# MPU-9250_Breakout.net
KiCad netlist of a schematic drawn in EAGLE
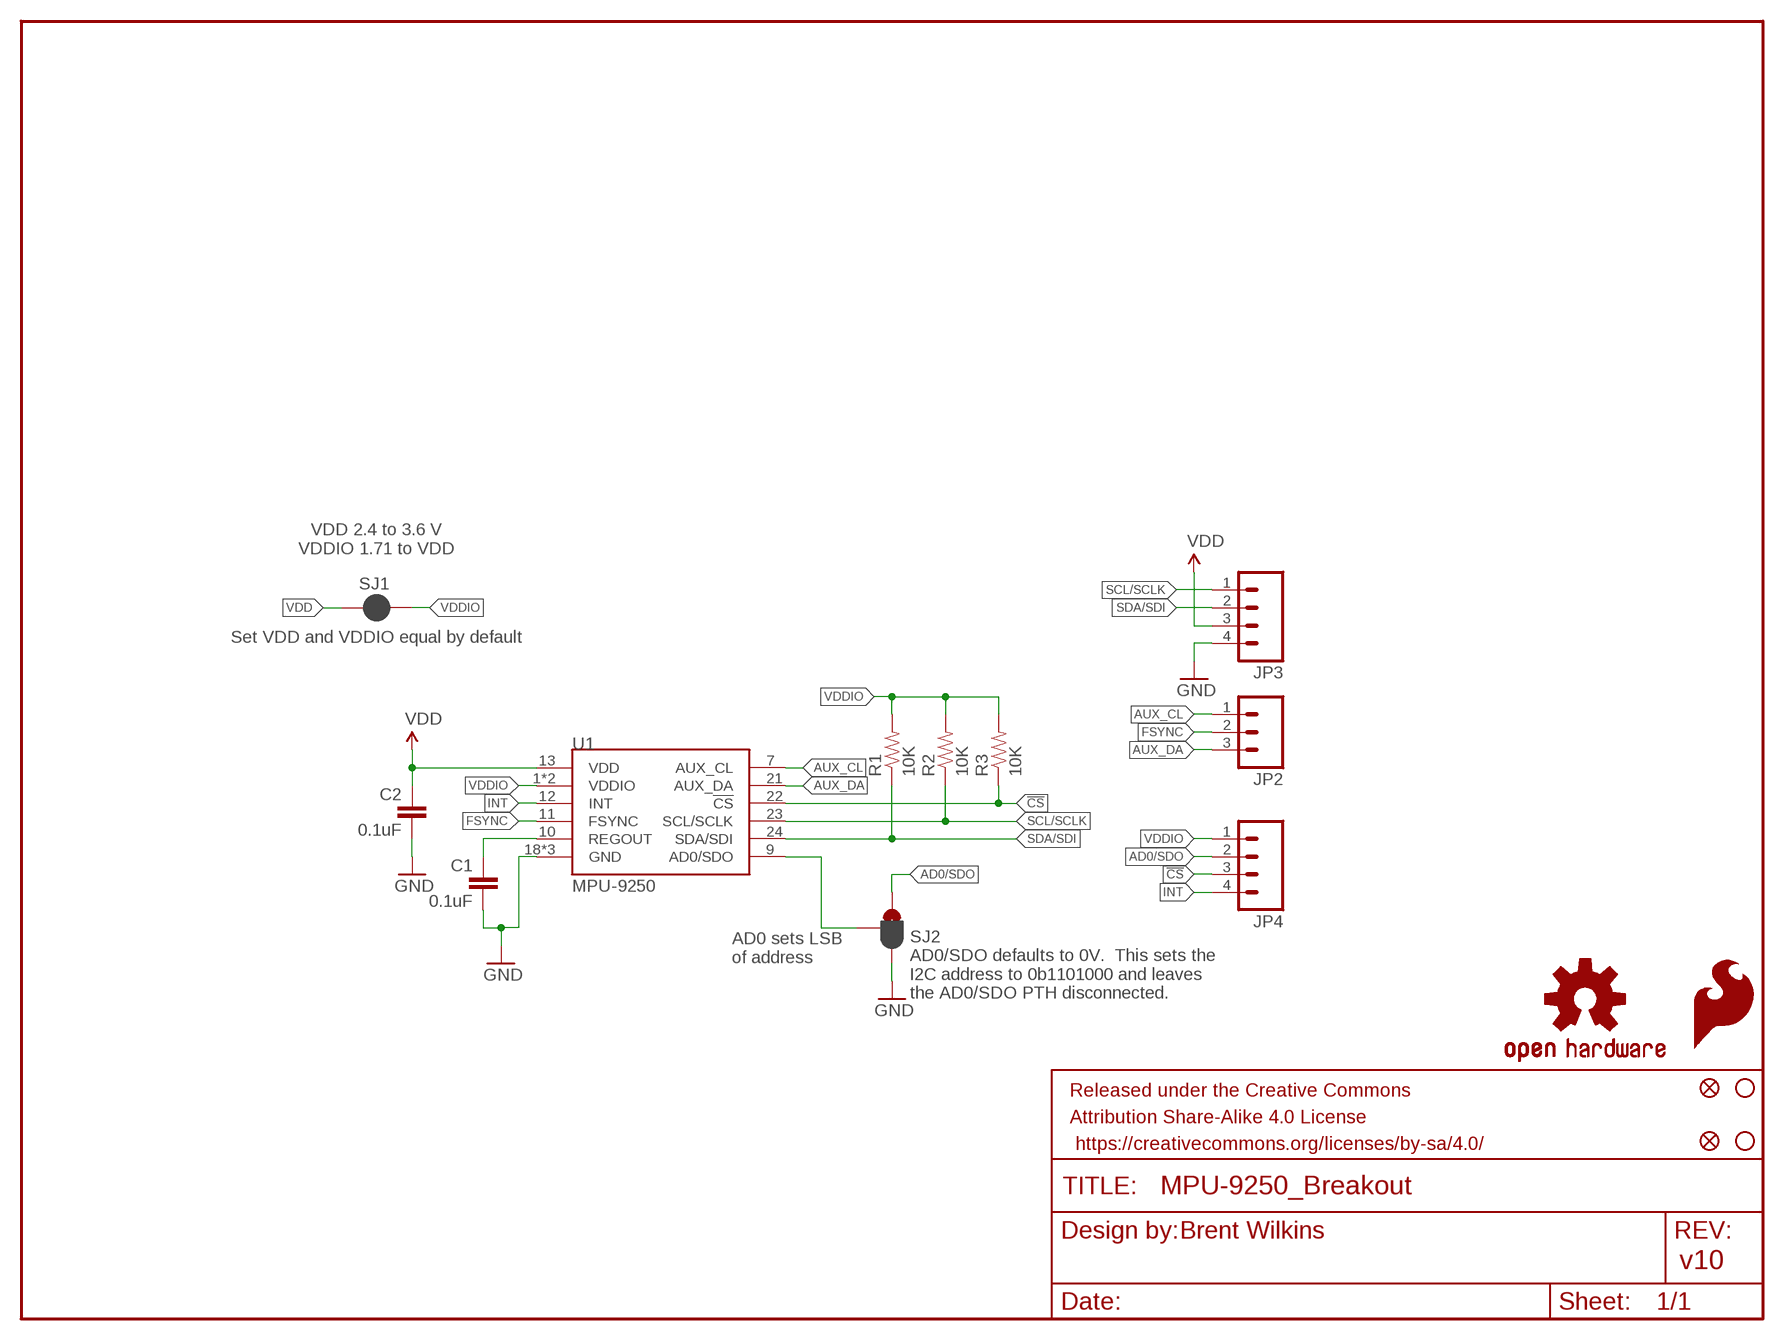
[diagram p0: schematic, sheet 1]

(export (version "E")
  (design (tool "Eeschema 10.0.6"))
  (components
    (comp (ref "C1")
      (value "0.1uF")
      (footprint "eagle-import:0603-CAP")
      (libsource (lib "eagle-import") (part "0.1UF-25V(+80/-20%)(0603)"))
    )
    (comp (ref "C2")
      (value "0.1uF")
      (footprint "eagle-import:0603-CAP")
      (libsource (lib "eagle-import") (part "0.1UF-25V(+80/-20%)(0603)"))
    )
    (comp (ref "FID1")
      (value "FIDUCIAL1X2")
      (footprint "eagle-import:FIDUCIAL-1X2")
      (libsource (lib "eagle-import") (part "FIDUCIAL1X2"))
    )
    (comp (ref "FID2")
      (value "FIDUCIAL1X2")
      (footprint "eagle-import:FIDUCIAL-1X2")
      (libsource (lib "eagle-import") (part "FIDUCIAL1X2"))
    )
    (comp (ref "FRAME1")
      (value "FRAME-LETTER")
      (footprint "eagle-import:CREATIVE_COMMONS")
      (libsource (lib "eagle-import") (part "FRAME-LETTER"))
    )
    (comp (ref "JP2")
      (value "M03PTH")
      (footprint "eagle-import:1X03")
      (libsource (lib "eagle-import") (part "M03PTH"))
    )
    (comp (ref "JP3")
      (value "M04PTH")
      (footprint "eagle-import:1X04")
      (libsource (lib "eagle-import") (part "M04PTH"))
    )
    (comp (ref "JP4")
      (value "M04PTH")
      (footprint "eagle-import:1X04")
      (libsource (lib "eagle-import") (part "M04PTH"))
    )
    (comp (ref "LOGO1")
      (value "SFE_LOGO_FLAME.1_INCH")
      (footprint "eagle-import:SFE_LOGO_FLAME_.1")
      (libsource (lib "eagle-import") (part "SFE_LOGO_FLAME.1_INCH"))
    )
    (comp (ref "LOGO2")
      (value "OSHW-LOGOS")
      (footprint "eagle-import:OSHW-LOGO-S")
      (libsource (lib "eagle-import") (part "OSHW-LOGOS"))
    )
    (comp (ref "R1")
      (value "10K")
      (footprint "eagle-import:0603-RES")
      (libsource (lib "eagle-import") (part "10KOHM-1/10W-1%(0603)0603"))
    )
    (comp (ref "R2")
      (value "10K")
      (footprint "eagle-import:0603-RES")
      (libsource (lib "eagle-import") (part "10KOHM-1/10W-1%(0603)0603"))
    )
    (comp (ref "R3")
      (value "10K")
      (footprint "eagle-import:0603-RES")
      (libsource (lib "eagle-import") (part "10KOHM-1/10W-1%(0603)0603"))
    )
    (comp (ref "SJ1")
      (value "JUMPER-PAD-2-NC_BY_PASTEFULL-BOX-SILK")
      (footprint "eagle-import:PAD-JUMPER-2-NC_BY_PASTE_YES_SILK_FULL_BOX")
      (libsource (lib "eagle-import") (part "JUMPER-PAD-2-NC_BY_PASTEFULL-BOX-SILK"))
    )
    (comp (ref "SJ2")
      (value "JUMPER_PAD-3-1&2_NC_BY_PASTE")
      (footprint "eagle-import:PAD-HUMPER-3-1&2_NC_BY_PASTE_YES_SILK_FULL_BOX")
      (libsource (lib "eagle-import") (part "JUMPER_PAD-3-1&2_NC_BY_PASTE"))
    )
    (comp (ref "STANDOFF1")
      (value "STAND-OFF")
      (footprint "eagle-import:STAND-OFF")
      (libsource (lib "eagle-import") (part "STAND-OFF"))
    )
    (comp (ref "STANDOFF2")
      (value "STAND-OFF")
      (footprint "eagle-import:STAND-OFF")
      (libsource (lib "eagle-import") (part "STAND-OFF"))
    )
    (comp (ref "U1")
      (value "MPU-9250")
      (footprint "eagle-import:QFN24_PAD")
      (libsource (lib "eagle-import") (part "MPU-9250"))
    )
  )
  (nets
    (net (code "1") (name "/~{CS}") (class "Default")
      (node (ref "JP4") (pin "3") (pinfunction "3_3") (pintype "passive"))
      (node (ref "R3") (pin "1") (pinfunction "1_1") (pintype "passive"))
      (node (ref "U1") (pin "22") (pinfunction "~{CS}_22") (pintype "bidirectional"))
    )
    (net (code "2") (name "AD0{slash}SDO") (class "Default")
      (node (ref "JP4") (pin "2") (pinfunction "2_2") (pintype "passive"))
      (node (ref "SJ2") (pin "3") (pinfunction "3_3") (pintype "passive"))
    )
    (net (code "3") (name "AUX_CL") (class "Default")
      (node (ref "JP2") (pin "1") (pinfunction "1_1") (pintype "passive"))
      (node (ref "U1") (pin "7") (pinfunction "AUX_CL_7") (pintype "bidirectional"))
    )
    (net (code "4") (name "AUX_DA") (class "Default")
      (node (ref "JP2") (pin "3") (pinfunction "3_3") (pintype "passive"))
      (node (ref "U1") (pin "21") (pinfunction "AUX_DA_21") (pintype "bidirectional"))
    )
    (net (code "5") (name "FSYNC") (class "Default")
      (node (ref "JP2") (pin "2") (pinfunction "2_2") (pintype "passive"))
      (node (ref "U1") (pin "11") (pinfunction "FSYNC_11") (pintype "bidirectional"))
    )
    (net (code "6") (name "GND") (class "Default")
      (node (ref "C1") (pin "2") (pinfunction "2_2") (pintype "passive"))
      (node (ref "C2") (pin "2") (pinfunction "2_2") (pintype "passive"))
      (node (ref "JP3") (pin "4") (pinfunction "4_4") (pintype "passive"))
      (node (ref "SJ2") (pin "1") (pinfunction "1_1") (pintype "passive"))
      (node (ref "U1") (pin "18") (pinfunction "GND_18") (pintype "bidirectional"))
      (node (ref "U1") (pin "20") (pinfunction "GND_20") (pintype "bidirectional"))
      (node (ref "U1") (pin "CENTER") (pinfunction "GND_CENTER") (pintype "bidirectional"))
    )
    (net (code "7") (name "INT") (class "Default")
      (node (ref "JP4") (pin "4") (pinfunction "4_4") (pintype "passive"))
      (node (ref "U1") (pin "12") (pinfunction "INT_12") (pintype "bidirectional"))
    )
    (net (code "8") (name "Net-(U1-AD0{slash}SDO)") (class "Default")
      (node (ref "SJ2") (pin "2") (pinfunction "2_2") (pintype "passive"))
      (node (ref "U1") (pin "9") (pinfunction "AD0/SDO_9") (pintype "bidirectional"))
    )
    (net (code "9") (name "Net-(U1-REGOUT)") (class "Default")
      (node (ref "C1") (pin "1") (pinfunction "1_1") (pintype "passive"))
      (node (ref "U1") (pin "10") (pinfunction "REGOUT_10") (pintype "bidirectional"))
    )
    (net (code "10") (name "SCL{slash}SCLK") (class "Default")
      (node (ref "JP3") (pin "1") (pinfunction "1_1") (pintype "passive"))
      (node (ref "R2") (pin "1") (pinfunction "1_1") (pintype "passive"))
      (node (ref "U1") (pin "23") (pinfunction "SCL/SCLK_23") (pintype "bidirectional"))
    )
    (net (code "11") (name "SDA{slash}SDI") (class "Default")
      (node (ref "JP3") (pin "2") (pinfunction "2_2") (pintype "passive"))
      (node (ref "R1") (pin "1") (pinfunction "1_1") (pintype "passive"))
      (node (ref "U1") (pin "24") (pinfunction "SDA/SDI_24") (pintype "bidirectional"))
    )
    (net (code "12") (name "VDD") (class "Default")
      (node (ref "C2") (pin "1") (pinfunction "1_1") (pintype "passive"))
      (node (ref "JP3") (pin "3") (pinfunction "3_3") (pintype "passive"))
      (node (ref "SJ1") (pin "1") (pinfunction "1_1") (pintype "passive"))
      (node (ref "U1") (pin "13") (pinfunction "VDD_13") (pintype "bidirectional"))
    )
    (net (code "13") (name "VDDIO") (class "Default")
      (node (ref "JP4") (pin "1") (pinfunction "1_1") (pintype "passive"))
      (node (ref "R1") (pin "2") (pinfunction "2_2") (pintype "passive"))
      (node (ref "R2") (pin "2") (pinfunction "2_2") (pintype "passive"))
      (node (ref "R3") (pin "2") (pinfunction "2_2") (pintype "passive"))
      (node (ref "SJ1") (pin "2") (pinfunction "2_2") (pintype "passive"))
      (node (ref "U1") (pin "1") (pinfunction "VDDIO_1") (pintype "bidirectional"))
      (node (ref "U1") (pin "8") (pinfunction "VDDIO_8") (pintype "bidirectional"))
    )
  )
)
